# sioboard.net
KiCad netlist of a schematic drawn in EAGLE
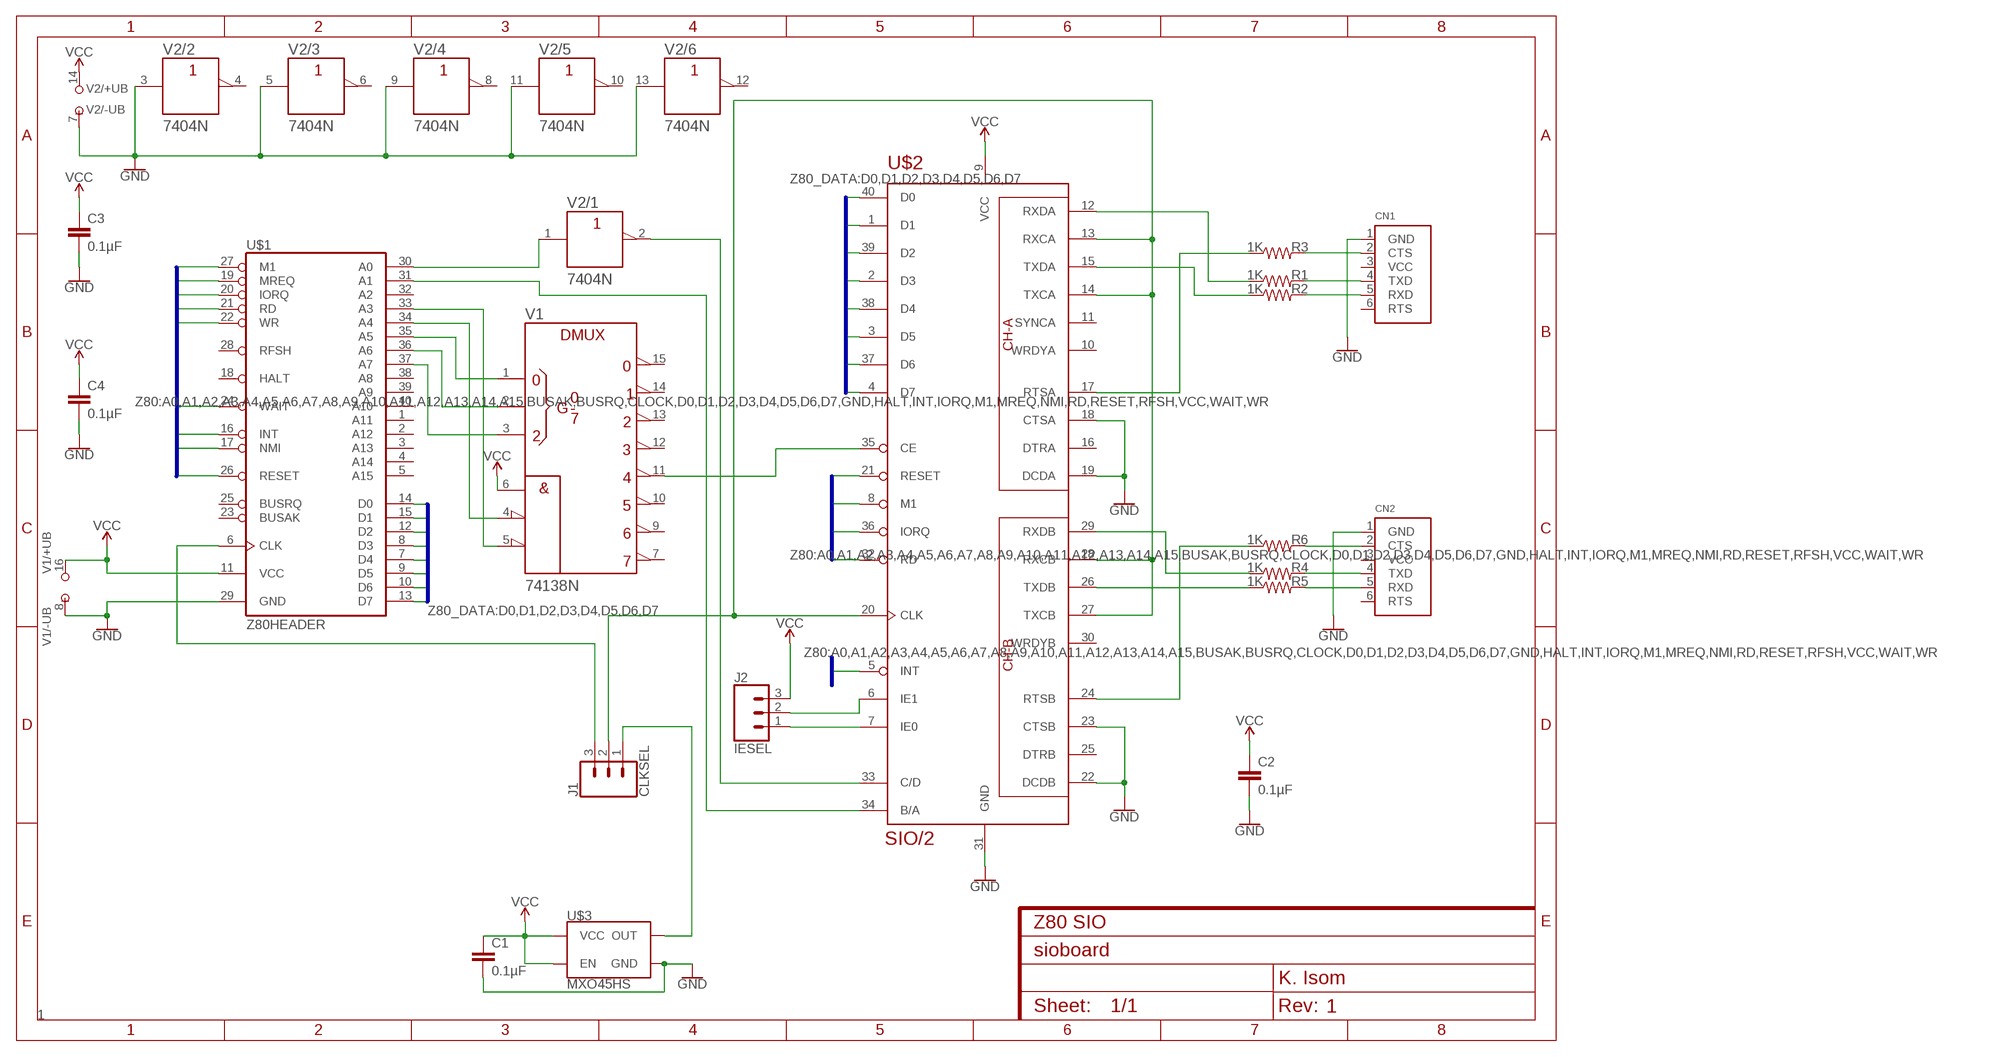
[diagram p0: schematic, sheet 1]

(export (version "E")
  (design (tool "Eeschema 10.0.6"))
  (components
    (comp (ref "C1")
      (value "0.1µF")
      (footprint "eagle-import:C2.5-3")
      (libsource (lib "eagle-import") (part "C2,5-3"))
    )
    (comp (ref "C2")
      (value "0.1µF")
      (footprint "eagle-import:C2.5-3")
      (libsource (lib "eagle-import") (part "C2,5-3"))
    )
    (comp (ref "C3")
      (value "0.1µF")
      (footprint "eagle-import:C2.5-3")
      (libsource (lib "eagle-import") (part "C2,5-3"))
    )
    (comp (ref "C4")
      (value "0.1µF")
      (footprint "eagle-import:C2.5-3")
      (libsource (lib "eagle-import") (part "C2,5-3"))
    )
    (comp (ref "CN1")
      (value "FTDIUSBCABLE")
      (footprint "eagle-import:1X06_ROUND")
      (libsource (lib "eagle-import") (part "FTDIUSBCABLE"))
    )
    (comp (ref "CN2")
      (value "FTDIUSBCABLE")
      (footprint "eagle-import:1X06_ROUND")
      (libsource (lib "eagle-import") (part "FTDIUSBCABLE"))
    )
    (comp (ref "J1")
      (value "CLKSEL")
      (footprint "eagle-import:1X03")
      (libsource (lib "eagle-import") (part "CONN_03"))
    )
    (comp (ref "J2")
      (value "IESEL")
      (footprint "eagle-import:1X03")
      (libsource (lib "eagle-import") (part "CONN_03"))
    )
    (comp (ref "R1")
      (value "1K")
      (footprint "eagle-import:AXIAL-0.3")
      (libsource (lib "eagle-import") (part "RESISTORAXIAL-0.3"))
    )
    (comp (ref "R2")
      (value "1K")
      (footprint "eagle-import:AXIAL-0.3")
      (libsource (lib "eagle-import") (part "RESISTORAXIAL-0.3"))
    )
    (comp (ref "R3")
      (value "1K")
      (footprint "eagle-import:AXIAL-0.3")
      (libsource (lib "eagle-import") (part "RESISTORAXIAL-0.3"))
    )
    (comp (ref "R4")
      (value "1K")
      (footprint "eagle-import:AXIAL-0.3")
      (libsource (lib "eagle-import") (part "RESISTORAXIAL-0.3"))
    )
    (comp (ref "R5")
      (value "1K")
      (footprint "eagle-import:AXIAL-0.3")
      (libsource (lib "eagle-import") (part "RESISTORAXIAL-0.3"))
    )
    (comp (ref "R6")
      (value "1K")
      (footprint "eagle-import:AXIAL-0.3")
      (libsource (lib "eagle-import") (part "RESISTORAXIAL-0.3"))
    )
    (comp (ref "U$1")
      (value "Z80HEADER")
      (footprint "eagle-import:2X20")
      (libsource (lib "eagle-import") (part "Z80HEADER"))
    )
    (comp (ref "U$2")
      (value "SIO/2")
      (footprint "eagle-import:DIL40")
      (libsource (lib "eagle-import") (part "SIO/2"))
    )
    (comp (ref "U$3")
      (value "MXO45HS")
      (footprint "eagle-import:DIL08-HALF")
      (libsource (lib "eagle-import") (part "MXO45HS"))
    )
    (comp (ref "V1")
      (value "74138N")
      (footprint "eagle-import:DIL16")
      (libsource (lib "eagle-import") (part "74138N"))
    )
    (comp (ref "V2")
      (value "7404N")
      (footprint "eagle-import:DIL14")
      (libsource (lib "eagle-import") (part "7404N"))
    )
  )
  (nets
    (net (code "27") (name "/D0") (class "Default")
      (node (ref "U$1") (pin "14") (pinfunction "D0_14") (pintype "bidirectional"))
      (node (ref "U$2") (pin "40") (pinfunction "D0_40") (pintype "bidirectional"))
    )
    (net (code "28") (name "/D1") (class "Default")
      (node (ref "U$1") (pin "15") (pinfunction "D1_15") (pintype "bidirectional"))
      (node (ref "U$2") (pin "1") (pinfunction "D1_1") (pintype "bidirectional"))
    )
    (net (code "29") (name "/D2") (class "Default")
      (node (ref "U$1") (pin "12") (pinfunction "D2_12") (pintype "bidirectional"))
      (node (ref "U$2") (pin "39") (pinfunction "D2_39") (pintype "bidirectional"))
    )
    (net (code "30") (name "/D3") (class "Default")
      (node (ref "U$1") (pin "8") (pinfunction "D3_8") (pintype "bidirectional"))
      (node (ref "U$2") (pin "2") (pinfunction "D3_2") (pintype "bidirectional"))
    )
    (net (code "31") (name "/D4") (class "Default")
      (node (ref "U$1") (pin "7") (pinfunction "D4_7") (pintype "bidirectional"))
      (node (ref "U$2") (pin "38") (pinfunction "D4_38") (pintype "bidirectional"))
    )
    (net (code "32") (name "/D5") (class "Default")
      (node (ref "U$1") (pin "9") (pinfunction "D5_9") (pintype "bidirectional"))
      (node (ref "U$2") (pin "3") (pinfunction "D5_3") (pintype "bidirectional"))
    )
    (net (code "33") (name "/D6") (class "Default")
      (node (ref "U$1") (pin "10") (pinfunction "D6_10") (pintype "bidirectional"))
      (node (ref "U$2") (pin "37") (pinfunction "D6_37") (pintype "bidirectional"))
    )
    (net (code "34") (name "/D7") (class "Default")
      (node (ref "U$1") (pin "13") (pinfunction "D7_13") (pintype "bidirectional"))
      (node (ref "U$2") (pin "4") (pinfunction "D7_4") (pintype "bidirectional"))
    )
    (net (code "35") (name "/INT") (class "Default")
      (node (ref "U$1") (pin "16") (pinfunction "INT_16") (pintype "input"))
      (node (ref "U$2") (pin "5") (pinfunction "INT_5") (pintype "bidirectional"))
    )
    (net (code "36") (name "/IORQ") (class "Default")
      (node (ref "U$1") (pin "20") (pinfunction "IORQ_20") (pintype "output"))
      (node (ref "U$2") (pin "36") (pinfunction "IORQ_36") (pintype "input"))
    )
    (net (code "37") (name "/M1") (class "Default")
      (node (ref "U$1") (pin "27") (pinfunction "M1_27") (pintype "output"))
      (node (ref "U$2") (pin "8") (pinfunction "M1_8") (pintype "input"))
    )
    (net (code "38") (name "/RD") (class "Default")
      (node (ref "U$1") (pin "21") (pinfunction "RD_21") (pintype "output"))
      (node (ref "U$2") (pin "32") (pinfunction "RD_32") (pintype "input"))
    )
    (net (code "39") (name "/RESET") (class "Default")
      (node (ref "U$1") (pin "26") (pinfunction "RESET_26") (pintype "input"))
      (node (ref "U$2") (pin "21") (pinfunction "RESET_21") (pintype "input"))
    )
    (net (code "42") (name "GND") (class "Default")
      (node (ref "C1") (pin "2") (pinfunction "2_2") (pintype "passive"))
      (node (ref "C2") (pin "2") (pinfunction "2_2") (pintype "passive"))
      (node (ref "C3") (pin "2") (pinfunction "2_2") (pintype "passive"))
      (node (ref "C4") (pin "2") (pinfunction "2_2") (pintype "passive"))
      (node (ref "CN1") (pin "1") (pinfunction "GND_1") (pintype "bidirectional"))
      (node (ref "CN2") (pin "1") (pinfunction "GND_1") (pintype "bidirectional"))
      (node (ref "U$1") (pin "29") (pinfunction "GND_29") (pintype "power_in"))
      (node (ref "U$2") (pin "18") (pinfunction "CTSA_18") (pintype "bidirectional"))
      (node (ref "U$2") (pin "19") (pinfunction "DCDA_19") (pintype "bidirectional"))
      (node (ref "U$2") (pin "22") (pinfunction "DCDB_22") (pintype "bidirectional"))
      (node (ref "U$2") (pin "23") (pinfunction "CTSB_23") (pintype "bidirectional"))
      (node (ref "U$2") (pin "31") (pinfunction "GND_31") (pintype "power_in"))
      (node (ref "U$3") (pin "4") (pinfunction "GND_4") (pintype "bidirectional"))
      (node (ref "V1") (pin "8") (pinfunction "-UB_8") (pintype "power_in"))
      (node (ref "V2") (pin "11") (pinfunction "A_11") (pintype "input"))
      (node (ref "V2") (pin "13") (pinfunction "A_13") (pintype "input"))
      (node (ref "V2") (pin "3") (pinfunction "A_3") (pintype "input"))
      (node (ref "V2") (pin "5") (pinfunction "A_5") (pintype "input"))
      (node (ref "V2") (pin "7") (pinfunction "-UB_7") (pintype "power_in"))
      (node (ref "V2") (pin "9") (pinfunction "A_9") (pintype "input"))
    )
    (net (code "43") (name "Net-(CN1-CTS)") (class "Default")
      (node (ref "CN1") (pin "2") (pinfunction "CTS_2") (pintype "bidirectional"))
      (node (ref "R3") (pin "P$2") (pinfunction "2_P$2") (pintype "passive"))
    )
    (net (code "44") (name "Net-(CN1-RXD)") (class "Default")
      (node (ref "CN1") (pin "5") (pinfunction "RXD_5") (pintype "bidirectional"))
      (node (ref "R2") (pin "P$2") (pinfunction "2_P$2") (pintype "passive"))
    )
    (net (code "45") (name "Net-(CN1-TXD)") (class "Default")
      (node (ref "CN1") (pin "4") (pinfunction "TXD_4") (pintype "bidirectional"))
      (node (ref "R1") (pin "P$2") (pinfunction "2_P$2") (pintype "passive"))
    )
    (net (code "46") (name "Net-(CN2-CTS)") (class "Default")
      (node (ref "CN2") (pin "2") (pinfunction "CTS_2") (pintype "bidirectional"))
      (node (ref "R6") (pin "P$2") (pinfunction "2_P$2") (pintype "passive"))
    )
    (net (code "47") (name "Net-(CN2-RXD)") (class "Default")
      (node (ref "CN2") (pin "5") (pinfunction "RXD_5") (pintype "bidirectional"))
      (node (ref "R5") (pin "P$2") (pinfunction "2_P$2") (pintype "passive"))
    )
    (net (code "48") (name "Net-(CN2-TXD)") (class "Default")
      (node (ref "CN2") (pin "4") (pinfunction "TXD_4") (pintype "bidirectional"))
      (node (ref "R4") (pin "P$2") (pinfunction "2_P$2") (pintype "passive"))
    )
    (net (code "49") (name "Net-(R1-1)") (class "Default")
      (node (ref "R1") (pin "P$1") (pinfunction "1_P$1") (pintype "passive"))
      (node (ref "U$2") (pin "12") (pinfunction "RXDA_12") (pintype "bidirectional"))
    )
    (net (code "50") (name "Net-(R2-1)") (class "Default")
      (node (ref "R2") (pin "P$1") (pinfunction "1_P$1") (pintype "passive"))
      (node (ref "U$2") (pin "15") (pinfunction "TXDA_15") (pintype "bidirectional"))
    )
    (net (code "51") (name "Net-(R3-1)") (class "Default")
      (node (ref "R3") (pin "P$1") (pinfunction "1_P$1") (pintype "passive"))
      (node (ref "U$2") (pin "17") (pinfunction "RTSA_17") (pintype "bidirectional"))
    )
    (net (code "52") (name "Net-(R4-1)") (class "Default")
      (node (ref "R4") (pin "P$1") (pinfunction "1_P$1") (pintype "passive"))
      (node (ref "U$2") (pin "29") (pinfunction "RXDB_29") (pintype "bidirectional"))
    )
    (net (code "53") (name "Net-(R5-1)") (class "Default")
      (node (ref "R5") (pin "P$1") (pinfunction "1_P$1") (pintype "passive"))
      (node (ref "U$2") (pin "26") (pinfunction "TXDB_26") (pintype "bidirectional"))
    )
    (net (code "54") (name "Net-(R6-1)") (class "Default")
      (node (ref "R6") (pin "P$1") (pinfunction "1_P$1") (pintype "passive"))
      (node (ref "U$2") (pin "24") (pinfunction "RTSB_24") (pintype "bidirectional"))
    )
    (net (code "55") (name "Net-(U$1-A0)") (class "Default")
      (node (ref "U$1") (pin "30") (pinfunction "A0_30") (pintype "output"))
      (node (ref "V2") (pin "1") (pinfunction "A_1") (pintype "input"))
    )
    (net (code "56") (name "Net-(U$1-A1)") (class "Default")
      (node (ref "U$1") (pin "31") (pinfunction "A1_31") (pintype "output"))
      (node (ref "U$2") (pin "34") (pinfunction "B/A_34") (pintype "bidirectional"))
    )
    (net (code "57") (name "Net-(U$1-A3)") (class "Default")
      (node (ref "U$1") (pin "33") (pinfunction "A3_33") (pintype "output"))
      (node (ref "V1") (pin "5") (pinfunction "~{G2B}_5") (pintype "input"))
    )
    (net (code "58") (name "Net-(U$1-A4)") (class "Default")
      (node (ref "U$1") (pin "34") (pinfunction "A4_34") (pintype "output"))
      (node (ref "V1") (pin "4") (pinfunction "~{G2A}_4") (pintype "input"))
    )
    (net (code "59") (name "Net-(U$1-A5)") (class "Default")
      (node (ref "U$1") (pin "35") (pinfunction "A5_35") (pintype "output"))
      (node (ref "V1") (pin "1") (pinfunction "A_1") (pintype "input"))
    )
    (net (code "60") (name "Net-(U$1-A6)") (class "Default")
      (node (ref "U$1") (pin "36") (pinfunction "A6_36") (pintype "output"))
      (node (ref "V1") (pin "2") (pinfunction "B_2") (pintype "input"))
    )
    (net (code "61") (name "Net-(U$1-A7)") (class "Default")
      (node (ref "U$1") (pin "37") (pinfunction "A7_37") (pintype "output"))
      (node (ref "V1") (pin "3") (pinfunction "C_3") (pintype "input"))
    )
    (net (code "62") (name "Net-(U$1-CLK)") (class "Default")
      (node (ref "J1") (pin "3") (pinfunction "3_3") (pintype "passive"))
      (node (ref "U$1") (pin "6") (pinfunction "CLK_6") (pintype "input"))
    )
    (net (code "63") (name "Net-(U$2-CE)") (class "Default")
      (node (ref "U$2") (pin "35") (pinfunction "CE_35") (pintype "input"))
      (node (ref "V1") (pin "11") (pinfunction "Y4_11") (pintype "output"))
    )
    (net (code "64") (name "Net-(U$2-CLK)") (class "Default")
      (node (ref "J1") (pin "2") (pinfunction "2_2") (pintype "passive"))
      (node (ref "U$2") (pin "13") (pinfunction "RXCA_13") (pintype "bidirectional"))
      (node (ref "U$2") (pin "14") (pinfunction "TXCA_14") (pintype "bidirectional"))
      (node (ref "U$2") (pin "20") (pinfunction "CLK_20") (pintype "input"))
      (node (ref "U$2") (pin "27") (pinfunction "TXCB_27") (pintype "bidirectional"))
      (node (ref "U$2") (pin "28") (pinfunction "RXCB_28") (pintype "bidirectional"))
    )
    (net (code "65") (name "Net-(U$2-C{slash}D)") (class "Default")
      (node (ref "U$2") (pin "33") (pinfunction "C/D_33") (pintype "bidirectional"))
      (node (ref "V2") (pin "2") (pinfunction "Y_2") (pintype "output"))
    )
    (net (code "66") (name "Net-(U$2-IE0)") (class "Default")
      (node (ref "J2") (pin "1") (pinfunction "1_1") (pintype "passive"))
      (node (ref "U$2") (pin "7") (pinfunction "IE0_7") (pintype "bidirectional"))
    )
    (net (code "67") (name "Net-(U$2-IE1)") (class "Default")
      (node (ref "J2") (pin "2") (pinfunction "2_2") (pintype "passive"))
      (node (ref "U$2") (pin "6") (pinfunction "IE1_6") (pintype "bidirectional"))
    )
    (net (code "68") (name "Net-(U$3-OUT)") (class "Default")
      (node (ref "J1") (pin "1") (pinfunction "1_1") (pintype "passive"))
      (node (ref "U$3") (pin "5") (pinfunction "OUT_5") (pintype "bidirectional"))
    )
    (net (code "69") (name "VCC") (class "Default")
      (node (ref "C1") (pin "1") (pinfunction "1_1") (pintype "passive"))
      (node (ref "C2") (pin "1") (pinfunction "1_1") (pintype "passive"))
      (node (ref "C3") (pin "1") (pinfunction "1_1") (pintype "passive"))
      (node (ref "C4") (pin "1") (pinfunction "1_1") (pintype "passive"))
      (node (ref "J2") (pin "3") (pinfunction "3_3") (pintype "passive"))
      (node (ref "U$1") (pin "11") (pinfunction "VCC_11") (pintype "power_in"))
      (node (ref "U$2") (pin "9") (pinfunction "VCC_9") (pintype "power_in"))
      (node (ref "U$3") (pin "1") (pinfunction "EN_1") (pintype "bidirectional"))
      (node (ref "U$3") (pin "8") (pinfunction "VCC_8") (pintype "bidirectional"))
      (node (ref "V1") (pin "16") (pinfunction "+UB_16") (pintype "power_in"))
      (node (ref "V1") (pin "6") (pinfunction "G1_6") (pintype "input"))
      (node (ref "V2") (pin "14") (pinfunction "+UB_14") (pintype "power_in"))
    )
    (net (code "70") (name "unconnected-(CN1-RTS-Pad6)") (class "Default")
      (node (ref "CN1") (pin "6") (pinfunction "RTS_6") (pintype "bidirectional"))
    )
    (net (code "71") (name "unconnected-(CN1-VCC-Pad3)") (class "Default")
      (node (ref "CN1") (pin "3") (pinfunction "VCC_3") (pintype "bidirectional"))
    )
    (net (code "72") (name "unconnected-(CN2-RTS-Pad6)") (class "Default")
      (node (ref "CN2") (pin "6") (pinfunction "RTS_6") (pintype "bidirectional"))
    )
    (net (code "73") (name "unconnected-(CN2-VCC-Pad3)") (class "Default")
      (node (ref "CN2") (pin "3") (pinfunction "VCC_3") (pintype "bidirectional"))
    )
    (net (code "74") (name "unconnected-(U$1-A2-Pad32)") (class "Default")
      (node (ref "U$1") (pin "32") (pinfunction "A2_32") (pintype "output"))
    )
    (net (code "75") (name "unconnected-(U$1-A8-Pad38)") (class "Default")
      (node (ref "U$1") (pin "38") (pinfunction "A8_38") (pintype "output"))
    )
    (net (code "76") (name "unconnected-(U$1-A9-Pad39)") (class "Default")
      (node (ref "U$1") (pin "39") (pinfunction "A9_39") (pintype "output"))
    )
    (net (code "77") (name "unconnected-(U$1-A10-Pad40)") (class "Default")
      (node (ref "U$1") (pin "40") (pinfunction "A10_40") (pintype "output"))
    )
    (net (code "78") (name "unconnected-(U$1-A11-Pad1)") (class "Default")
      (node (ref "U$1") (pin "1") (pinfunction "A11_1") (pintype "output"))
    )
    (net (code "79") (name "unconnected-(U$1-A12-Pad2)") (class "Default")
      (node (ref "U$1") (pin "2") (pinfunction "A12_2") (pintype "output"))
    )
    (net (code "80") (name "unconnected-(U$1-A13-Pad3)") (class "Default")
      (node (ref "U$1") (pin "3") (pinfunction "A13_3") (pintype "output"))
    )
    (net (code "81") (name "unconnected-(U$1-A14-Pad4)") (class "Default")
      (node (ref "U$1") (pin "4") (pinfunction "A14_4") (pintype "output"))
    )
    (net (code "82") (name "unconnected-(U$1-A15-Pad5)") (class "Default")
      (node (ref "U$1") (pin "5") (pinfunction "A15_5") (pintype "output"))
    )
    (net (code "83") (name "unconnected-(U$1-BUSAK-Pad23)") (class "Default")
      (node (ref "U$1") (pin "23") (pinfunction "BUSAK_23") (pintype "output"))
    )
    (net (code "84") (name "unconnected-(U$1-BUSRQ-Pad25)") (class "Default")
      (node (ref "U$1") (pin "25") (pinfunction "BUSRQ_25") (pintype "input"))
    )
    (net (code "85") (name "unconnected-(U$1-HALT-Pad18)") (class "Default")
      (node (ref "U$1") (pin "18") (pinfunction "HALT_18") (pintype "output"))
    )
    (net (code "86") (name "unconnected-(U$1-MREQ-Pad19)") (class "Default")
      (node (ref "U$1") (pin "19") (pinfunction "MREQ_19") (pintype "output"))
    )
    (net (code "87") (name "unconnected-(U$1-NMI-Pad17)") (class "Default")
      (node (ref "U$1") (pin "17") (pinfunction "NMI_17") (pintype "input"))
    )
    (net (code "88") (name "unconnected-(U$1-RFSH-Pad28)") (class "Default")
      (node (ref "U$1") (pin "28") (pinfunction "RFSH_28") (pintype "output"))
    )
    (net (code "89") (name "unconnected-(U$1-WAIT-Pad24)") (class "Default")
      (node (ref "U$1") (pin "24") (pinfunction "WAIT_24") (pintype "input"))
    )
    (net (code "90") (name "unconnected-(U$1-WR-Pad22)") (class "Default")
      (node (ref "U$1") (pin "22") (pinfunction "WR_22") (pintype "output"))
    )
    (net (code "91") (name "unconnected-(U$2-DTRA-Pad16)") (class "Default")
      (node (ref "U$2") (pin "16") (pinfunction "DTRA_16") (pintype "bidirectional"))
    )
    (net (code "92") (name "unconnected-(U$2-DTRB-Pad25)") (class "Default")
      (node (ref "U$2") (pin "25") (pinfunction "DTRB_25") (pintype "bidirectional"))
    )
    (net (code "93") (name "unconnected-(U$2-SYNCA-Pad11)") (class "Default")
      (node (ref "U$2") (pin "11") (pinfunction "SYNCA_11") (pintype "bidirectional"))
    )
    (net (code "94") (name "unconnected-(U$2-WRDYA-Pad10)") (class "Default")
      (node (ref "U$2") (pin "10") (pinfunction "WRDYA_10") (pintype "bidirectional"))
    )
    (net (code "95") (name "unconnected-(U$2-WRDYB-Pad30)") (class "Default")
      (node (ref "U$2") (pin "30") (pinfunction "WRDYB_30") (pintype "bidirectional"))
    )
    (net (code "96") (name "unconnected-(V1C-Y0-Pad15)") (class "Default")
      (node (ref "V1") (pin "15") (pinfunction "Y0_15") (pintype "output"))
    )
    (net (code "97") (name "unconnected-(V1C-Y1-Pad14)") (class "Default")
      (node (ref "V1") (pin "14") (pinfunction "Y1_14") (pintype "output"))
    )
    (net (code "98") (name "unconnected-(V1C-Y2-Pad13)") (class "Default")
      (node (ref "V1") (pin "13") (pinfunction "Y2_13") (pintype "output"))
    )
    (net (code "99") (name "unconnected-(V1C-Y3-Pad12)") (class "Default")
      (node (ref "V1") (pin "12") (pinfunction "Y3_12") (pintype "output"))
    )
    (net (code "100") (name "unconnected-(V1C-Y5-Pad10)") (class "Default")
      (node (ref "V1") (pin "10") (pinfunction "Y5_10") (pintype "output"))
    )
    (net (code "101") (name "unconnected-(V1C-Y6-Pad9)") (class "Default")
      (node (ref "V1") (pin "9") (pinfunction "Y6_9") (pintype "output"))
    )
    (net (code "102") (name "unconnected-(V1C-Y7-Pad7)") (class "Default")
      (node (ref "V1") (pin "7") (pinfunction "Y7_7") (pintype "output"))
    )
    (net (code "103") (name "unconnected-(V2D-Y-Pad4)") (class "Default")
      (node (ref "V2") (pin "4") (pinfunction "Y_4") (pintype "output"))
    )
    (net (code "104") (name "unconnected-(V2E-Y-Pad6)") (class "Default")
      (node (ref "V2") (pin "6") (pinfunction "Y_6") (pintype "output"))
    )
    (net (code "105") (name "unconnected-(V2F-Y-Pad8)") (class "Default")
      (node (ref "V2") (pin "8") (pinfunction "Y_8") (pintype "output"))
    )
    (net (code "106") (name "unconnected-(V2G-Y-Pad10)") (class "Default")
      (node (ref "V2") (pin "10") (pinfunction "Y_10") (pintype "output"))
    )
    (net (code "107") (name "unconnected-(V2H-Y-Pad12)") (class "Default")
      (node (ref "V2") (pin "12") (pinfunction "Y_12") (pintype "output"))
    )
  )
)
